# USB_Mux-v0_2.net
KiCad netlist of a schematic drawn in EAGLE
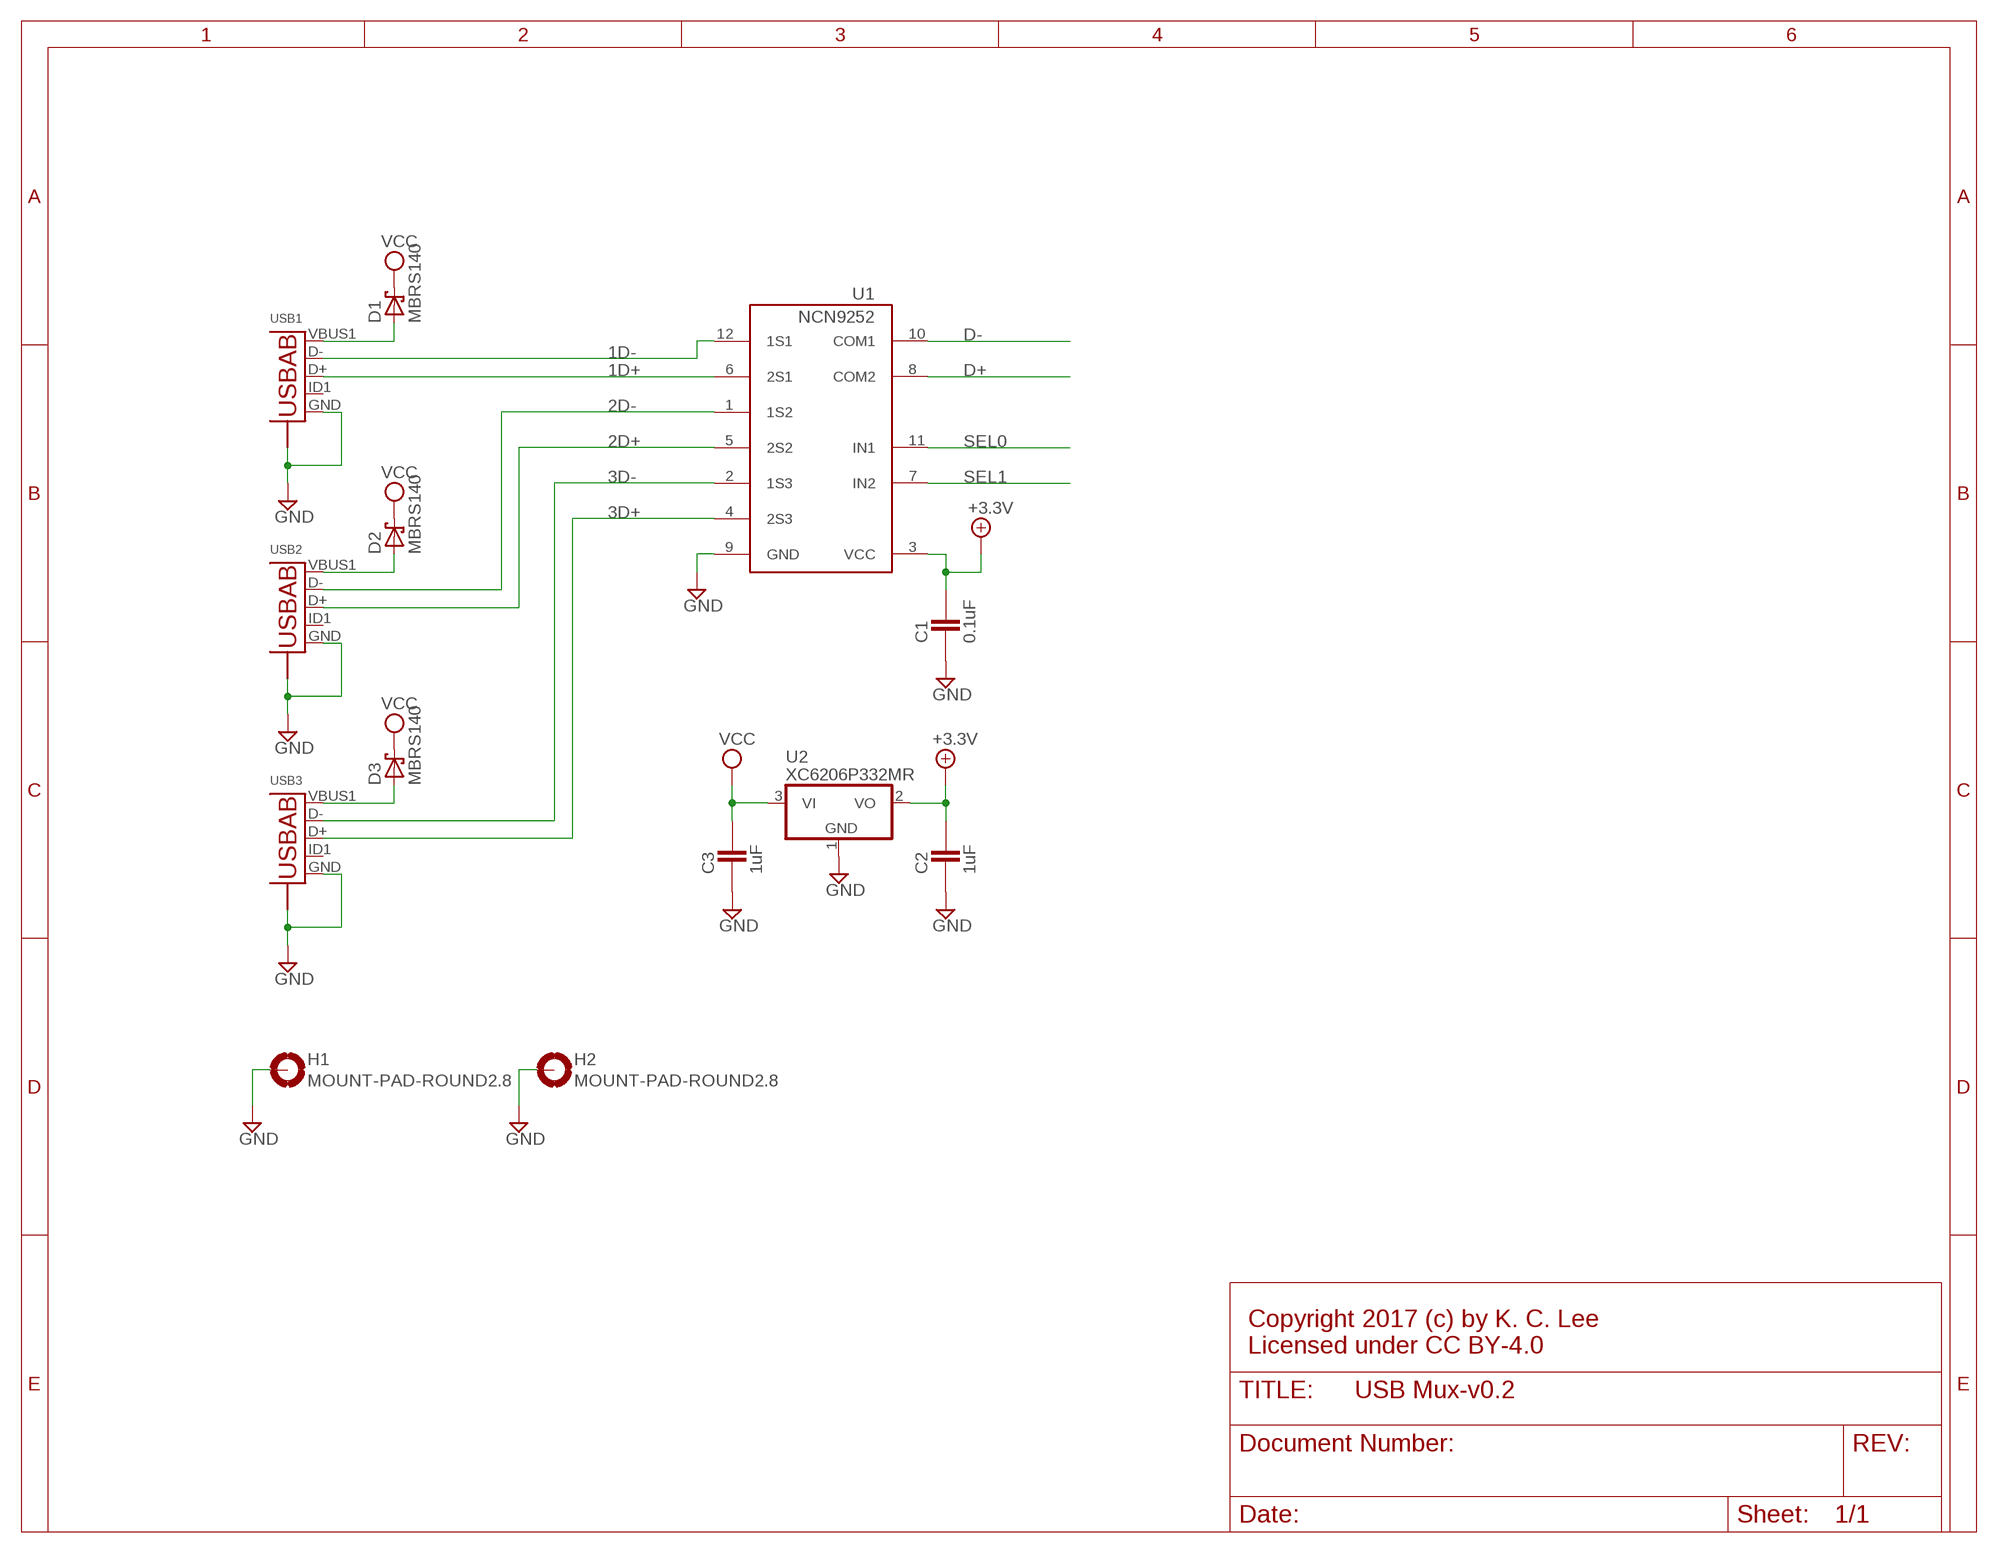
[diagram p0: schematic, sheet 1]

(export (version "E")
  (design (tool "Eeschema 10.0.6"))
  (components
    (comp (ref "C1")
      (value "0.1uF")
      (footprint "eagle-import:CAPC1608X92N")
      (fields (field (name "PARTNO") "0U1 0603"))
      (libsource (lib "eagle-import") (part "CAPACITOR_0603"))
    )
    (comp (ref "C2")
      (value "1uF")
      (footprint "eagle-import:CAPC1608X92N")
      (fields (field (name "PARTNO") "1UF 0603"))
      (libsource (lib "eagle-import") (part "CAPACITOR_0603"))
    )
    (comp (ref "C3")
      (value "1uF")
      (footprint "eagle-import:CAPC1608X92N")
      (fields (field (name "PARTNO") "1UF 0603"))
      (libsource (lib "eagle-import") (part "CAPACITOR_0603"))
    )
    (comp (ref "D1")
      (value "MBRS140")
      (footprint "eagle-import:DIOM5436X265N")
      (libsource (lib "eagle-import") (part "SCHOTTKY_SMB"))
    )
    (comp (ref "D2")
      (value "MBRS140")
      (footprint "eagle-import:DIOM5436X265N")
      (libsource (lib "eagle-import") (part "SCHOTTKY_SMB"))
    )
    (comp (ref "D3")
      (value "MBRS140")
      (footprint "eagle-import:DIOM5436X265N")
      (libsource (lib "eagle-import") (part "SCHOTTKY_SMB"))
    )
    (comp (ref "H1")
      (value "MOUNT-PAD-ROUND2.8")
      (footprint "eagle-import:2,8-PAD")
      (libsource (lib "eagle-import") (part "MOUNT-PAD-ROUND2.8"))
    )
    (comp (ref "H2")
      (value "MOUNT-PAD-ROUND2.8")
      (footprint "eagle-import:2,8-PAD")
      (libsource (lib "eagle-import") (part "MOUNT-PAD-ROUND2.8"))
    )
    (comp (ref "U1")
      (value "NCN9252")
      (footprint "eagle-import:UQN12")
      (libsource (lib "eagle-import") (part "NCN9252"))
    )
    (comp (ref "U2")
      (value "XC6206P332MR")
      (footprint "eagle-import:SOT95P280X135-3N")
      (libsource (lib "eagle-import") (part "MCP1700/TT"))
    )
    (comp (ref "USB1")
      (value "USB-ABBG-ORG")
      (footprint "eagle-import:USB-AB-MICRO-SMD_V03_SMT")
      (fields (field (name "PARTNO") "SMT MICRO USB CONNECTOR"))
      (libsource (lib "eagle-import") (part "USB-ABBG-ORG"))
    )
    (comp (ref "USB2")
      (value "USB-ABBG-ORG")
      (footprint "eagle-import:USB-AB-MICRO-SMD_V03_SMT")
      (fields (field (name "PARTNO") "SMT MICRO USB CONNECTOR"))
      (libsource (lib "eagle-import") (part "USB-ABBG-ORG"))
    )
    (comp (ref "USB3")
      (value "USB-ABBG-ORG")
      (footprint "eagle-import:USB-AB-MICRO-SMD_V03_SMT")
      (fields (field (name "PARTNO") "SMT MICRO USB CONNECTOR"))
      (libsource (lib "eagle-import") (part "USB-ABBG-ORG"))
    )
  )
  (nets
    (net (code "1") (name "+3.3V") (class "Default")
      (node (ref "C1") (pin "2") (pinfunction "2_2") (pintype "passive"))
      (node (ref "C2") (pin "2") (pinfunction "2_2") (pintype "passive"))
      (node (ref "U1") (pin "3") (pinfunction "VCC_3") (pintype "bidirectional"))
      (node (ref "U2") (pin "2") (pinfunction "VO_2") (pintype "passive"))
    )
    (net (code "2") (name "/1D+") (class "Default")
      (node (ref "U1") (pin "6") (pinfunction "2S1_6") (pintype "bidirectional"))
      (node (ref "USB1") (pin "D+") (pinfunction "D+_D+") (pintype "bidirectional"))
    )
    (net (code "3") (name "/1D-") (class "Default")
      (node (ref "U1") (pin "12") (pinfunction "1S1_12") (pintype "bidirectional"))
      (node (ref "USB1") (pin "D-") (pinfunction "D-_D-") (pintype "bidirectional"))
    )
    (net (code "4") (name "/2D+") (class "Default")
      (node (ref "U1") (pin "5") (pinfunction "2S2_5") (pintype "bidirectional"))
      (node (ref "USB2") (pin "D+") (pinfunction "D+_D+") (pintype "bidirectional"))
    )
    (net (code "5") (name "/2D-") (class "Default")
      (node (ref "U1") (pin "1") (pinfunction "1S2_1") (pintype "bidirectional"))
      (node (ref "USB2") (pin "D-") (pinfunction "D-_D-") (pintype "bidirectional"))
    )
    (net (code "6") (name "/3D+") (class "Default")
      (node (ref "U1") (pin "4") (pinfunction "2S3_4") (pintype "bidirectional"))
      (node (ref "USB3") (pin "D+") (pinfunction "D+_D+") (pintype "bidirectional"))
    )
    (net (code "7") (name "/3D-") (class "Default")
      (node (ref "U1") (pin "2") (pinfunction "1S3_2") (pintype "bidirectional"))
      (node (ref "USB3") (pin "D-") (pinfunction "D-_D-") (pintype "bidirectional"))
    )
    (net (code "8") (name "/D+") (class "Default")
      (node (ref "U1") (pin "8") (pinfunction "COM2_8") (pintype "bidirectional"))
    )
    (net (code "9") (name "/D-") (class "Default")
      (node (ref "U1") (pin "10") (pinfunction "COM1_10") (pintype "bidirectional"))
    )
    (net (code "10") (name "/SEL0") (class "Default")
      (node (ref "U1") (pin "11") (pinfunction "IN1_11") (pintype "bidirectional"))
    )
    (net (code "11") (name "/SEL1") (class "Default")
      (node (ref "U1") (pin "7") (pinfunction "IN2_7") (pintype "bidirectional"))
    )
    (net (code "12") (name "GND") (class "Default")
      (node (ref "C1") (pin "1") (pinfunction "1_1") (pintype "passive"))
      (node (ref "C2") (pin "1") (pinfunction "1_1") (pintype "passive"))
      (node (ref "C3") (pin "1") (pinfunction "1_1") (pintype "passive"))
      (node (ref "H1") (pin "B2,8") (pinfunction "MOUNT_B2,8") (pintype "passive"))
      (node (ref "H2") (pin "B2,8") (pinfunction "MOUNT_B2,8") (pintype "passive"))
      (node (ref "U1") (pin "9") (pinfunction "GND_9") (pintype "bidirectional"))
      (node (ref "U2") (pin "1") (pinfunction "GND_1") (pintype "passive"))
      (node (ref "USB1") (pin "GND") (pinfunction "GND_GND") (pintype "bidirectional"))
      (node (ref "USB1") (pin "S1") (pinfunction "S_S1") (pintype "bidirectional"))
      (node (ref "USB1") (pin "S2") (pinfunction "S_S2") (pintype "bidirectional"))
      (node (ref "USB1") (pin "S3") (pinfunction "S_S3") (pintype "bidirectional"))
      (node (ref "USB1") (pin "S4") (pinfunction "S_S4") (pintype "bidirectional"))
      (node (ref "USB2") (pin "GND") (pinfunction "GND_GND") (pintype "bidirectional"))
      (node (ref "USB2") (pin "S1") (pinfunction "S_S1") (pintype "bidirectional"))
      (node (ref "USB2") (pin "S2") (pinfunction "S_S2") (pintype "bidirectional"))
      (node (ref "USB2") (pin "S3") (pinfunction "S_S3") (pintype "bidirectional"))
      (node (ref "USB2") (pin "S4") (pinfunction "S_S4") (pintype "bidirectional"))
      (node (ref "USB3") (pin "GND") (pinfunction "GND_GND") (pintype "bidirectional"))
      (node (ref "USB3") (pin "S1") (pinfunction "S_S1") (pintype "bidirectional"))
      (node (ref "USB3") (pin "S2") (pinfunction "S_S2") (pintype "bidirectional"))
      (node (ref "USB3") (pin "S3") (pinfunction "S_S3") (pintype "bidirectional"))
      (node (ref "USB3") (pin "S4") (pinfunction "S_S4") (pintype "bidirectional"))
    )
    (net (code "13") (name "Net-(USB1-VBUS)") (class "Default")
      (node (ref "D1") (pin "A") (pinfunction "A_A") (pintype "passive"))
      (node (ref "USB1") (pin "VBUS1") (pinfunction "VBUS_VBUS1") (pintype "bidirectional"))
    )
    (net (code "14") (name "Net-(USB2-VBUS)") (class "Default")
      (node (ref "D2") (pin "A") (pinfunction "A_A") (pintype "passive"))
      (node (ref "USB2") (pin "VBUS1") (pinfunction "VBUS_VBUS1") (pintype "bidirectional"))
    )
    (net (code "15") (name "Net-(USB3-VBUS)") (class "Default")
      (node (ref "D3") (pin "A") (pinfunction "A_A") (pintype "passive"))
      (node (ref "USB3") (pin "VBUS1") (pinfunction "VBUS_VBUS1") (pintype "bidirectional"))
    )
    (net (code "16") (name "VCC") (class "Default")
      (node (ref "C3") (pin "2") (pinfunction "2_2") (pintype "passive"))
      (node (ref "D1") (pin "K") (pinfunction "K_K") (pintype "passive"))
      (node (ref "D2") (pin "K") (pinfunction "K_K") (pintype "passive"))
      (node (ref "D3") (pin "K") (pinfunction "K_K") (pintype "passive"))
      (node (ref "U2") (pin "3") (pinfunction "VI_3") (pintype "input"))
    )
    (net (code "17") (name "unconnected-(USB1-USBID-PadID1)") (class "Default")
      (node (ref "USB1") (pin "ID1") (pinfunction "USBID_ID1") (pintype "bidirectional"))
    )
    (net (code "18") (name "unconnected-(USB2-USBID-PadID1)") (class "Default")
      (node (ref "USB2") (pin "ID1") (pinfunction "USBID_ID1") (pintype "bidirectional"))
    )
    (net (code "19") (name "unconnected-(USB3-USBID-PadID1)") (class "Default")
      (node (ref "USB3") (pin "ID1") (pinfunction "USBID_ID1") (pintype "bidirectional"))
    )
  )
)
